# toolbox.net
KiCad netlist of a schematic drawn in EAGLE
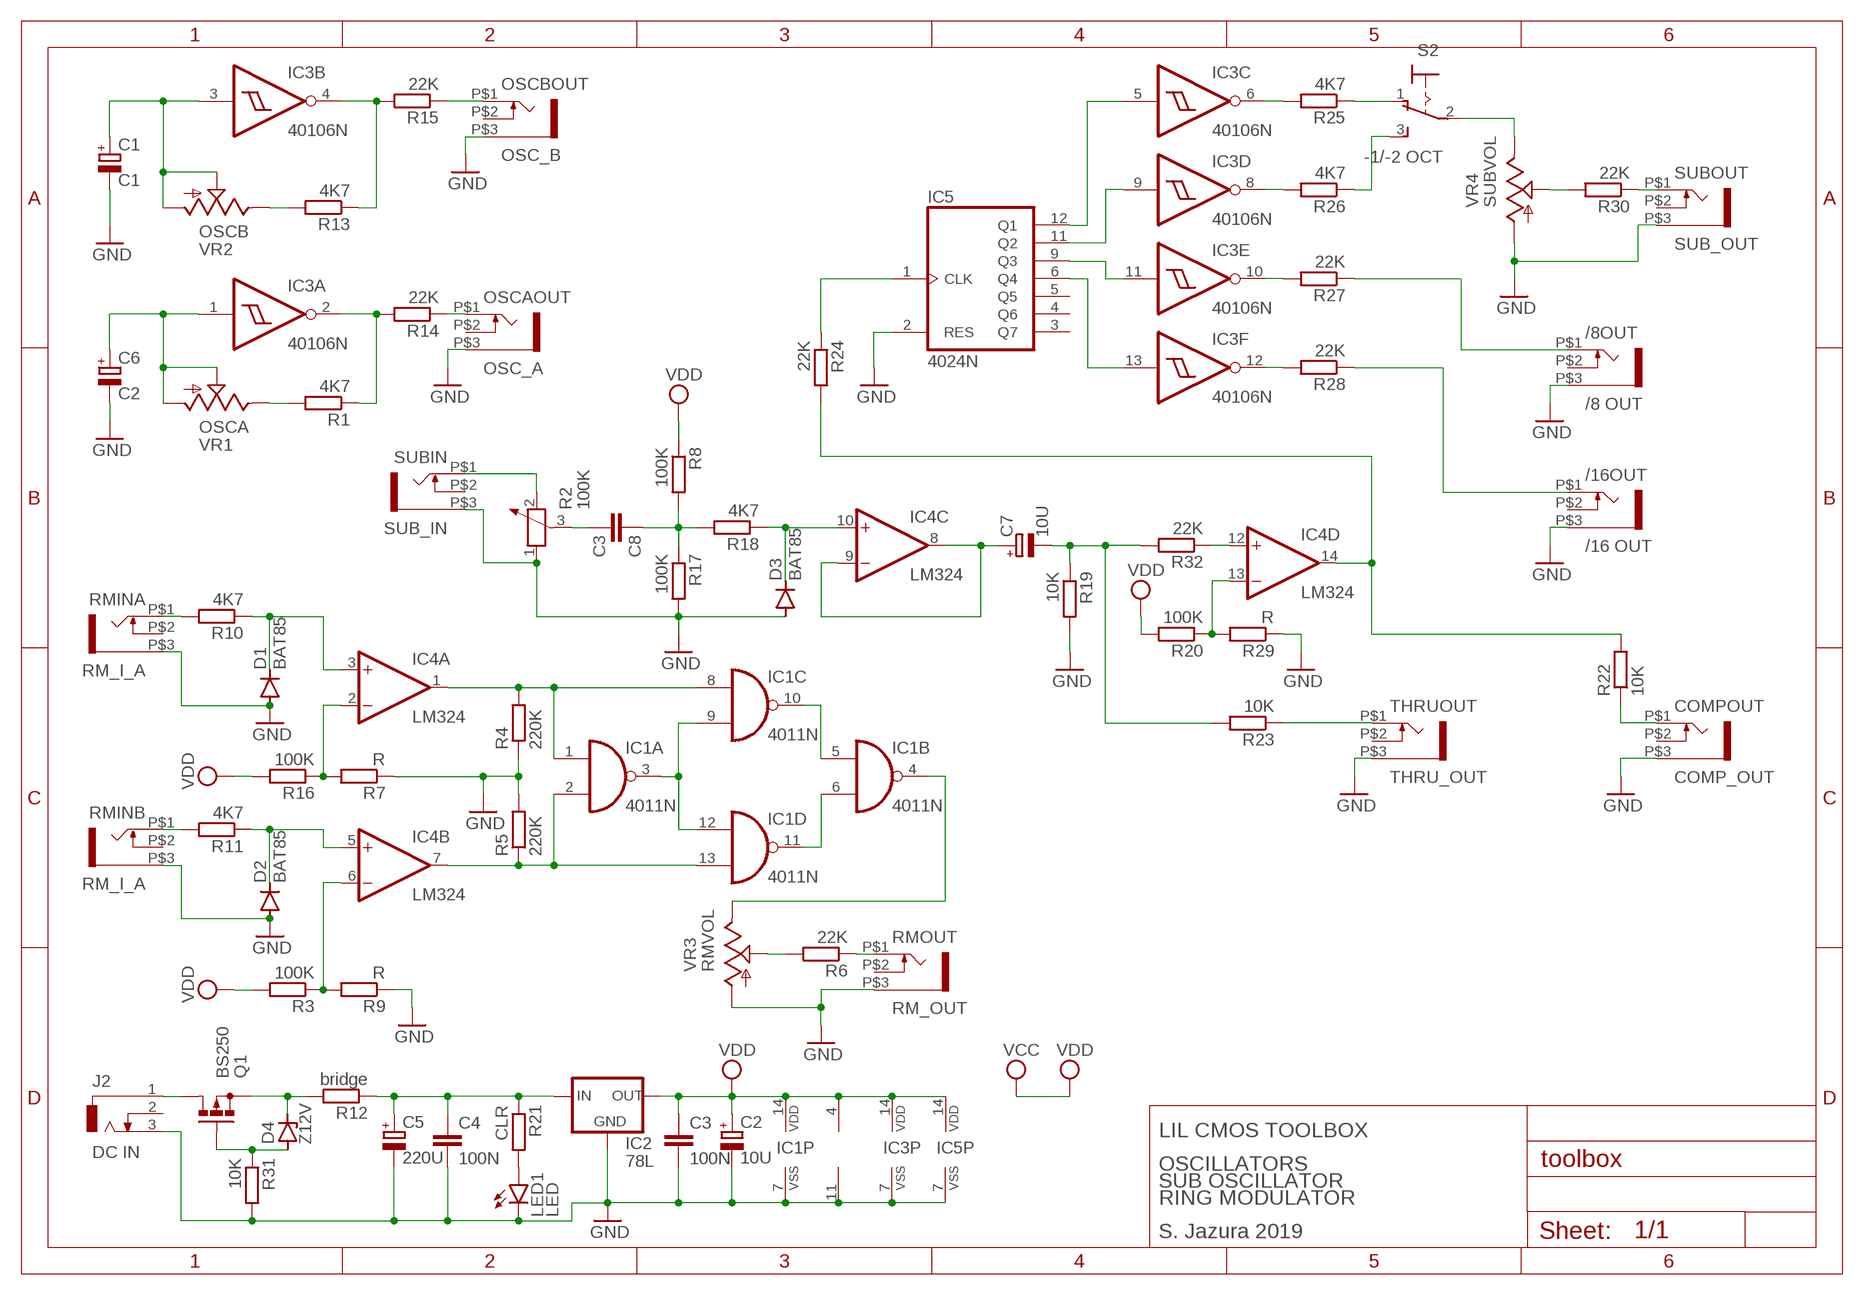
[diagram p0: schematic, sheet 1]

(export (version "E")
  (design (tool "Eeschema 10.0.6"))
  (components
    (comp (ref "/8OUT")
      (value "/8 OUT")
      (footprint "eagle-import:WQP-PJ301M-12_JACK")
      (libsource (lib "eagle-import") (part "WQP-PJ301M-12_JACK"))
    )
    (comp (ref "/16OUT")
      (value "/16 OUT")
      (footprint "eagle-import:WQP-PJ301M-12_JACK")
      (libsource (lib "eagle-import") (part "WQP-PJ301M-12_JACK"))
    )
    (comp (ref "C1")
      (value "C1")
      (footprint "eagle-import:000_4MM_CAP_STANDARD")
      (libsource (lib "eagle-import") (part "0_CPOL-EUE2-4"))
    )
    (comp (ref "C2")
      (value "10U")
      (footprint "eagle-import:000_4MM_CAP_STANDARD")
      (libsource (lib "eagle-import") (part "0_CPOL-EUE2-4"))
    )
    (comp (ref "C3")
      (value "100N")
      (footprint "eagle-import:000_5MM_DISC_STANDARD")
      (libsource (lib "eagle-import") (part "C-EU000_5MM_DISC"))
    )
    (comp (ref "C4")
      (value "100N")
      (footprint "eagle-import:000_5MM_DISC_STANDARD")
      (libsource (lib "eagle-import") (part "C-EU000_5MM_DISC"))
    )
    (comp (ref "C5")
      (value "220U")
      (footprint "eagle-import:E2,5-7")
      (libsource (lib "eagle-import") (part "CPOL-EUE2.5-7"))
    )
    (comp (ref "C6")
      (value "C2")
      (footprint "eagle-import:000_4MM_CAP_STANDARD")
      (libsource (lib "eagle-import") (part "0_CPOL-EUE2-4"))
    )
    (comp (ref "C7")
      (value "10U")
      (footprint "eagle-import:000_4MM_CAP_STANDARD")
      (libsource (lib "eagle-import") (part "0_CPOL-EUE2-4"))
    )
    (comp (ref "C8")
      (value "C3")
      (footprint "eagle-import:000_7,5MM_FOIL_STANDARD")
      (libsource (lib "eagle-import") (part "0_C-EU000_7,5MM_FOIL_STANDARD"))
    )
    (comp (ref "COMPOUT")
      (value "COMP_OUT")
      (footprint "eagle-import:WQP-PJ301M-12_JACK")
      (libsource (lib "eagle-import") (part "WQP-PJ301M-12_JACK"))
    )
    (comp (ref "D1")
      (value "BAT85")
      (footprint "eagle-import:DO35-7")
      (libsource (lib "eagle-import") (part "1N4148DO35-7"))
    )
    (comp (ref "D2")
      (value "BAT85")
      (footprint "eagle-import:DO35-7")
      (libsource (lib "eagle-import") (part "1N4148DO35-7"))
    )
    (comp (ref "D3")
      (value "BAT85")
      (footprint "eagle-import:DO35-7")
      (libsource (lib "eagle-import") (part "1N4148DO35-7"))
    )
    (comp (ref "D4")
      (value "Z12V")
      (footprint "eagle-import:DO34Z7")
      (libsource (lib "eagle-import") (part "BZV10"))
    )
    (comp (ref "IC1")
      (value "4011N")
      (footprint "eagle-import:DIL14")
      (libsource (lib "eagle-import") (part "4011N"))
    )
    (comp (ref "IC2")
      (value "78L")
      (footprint "eagle-import:000_78LXX_STANDARD")
      (libsource (lib "eagle-import") (part "78LXX"))
    )
    (comp (ref "IC3")
      (value "40106N")
      (footprint "eagle-import:DIL14")
      (libsource (lib "eagle-import") (part "40106N"))
    )
    (comp (ref "IC4")
      (value "LM324")
      (footprint "eagle-import:DIL14")
      (libsource (lib "eagle-import") (part "TL074P"))
    )
    (comp (ref "IC5")
      (value "4024N")
      (footprint "eagle-import:DIL14")
      (libsource (lib "eagle-import") (part "4024N"))
    )
    (comp (ref "J2")
      (value "DC IN")
      (footprint "eagle-import:DCJ0202")
      (libsource (lib "eagle-import") (part "DCJ0202"))
    )
    (comp (ref "LED1")
      (value "LED")
      (footprint "eagle-import:LED5MM")
      (libsource (lib "eagle-import") (part "LED5MM"))
    )
    (comp (ref "OSCAOUT")
      (value "OSC_A")
      (footprint "eagle-import:WQP-PJ301M-12_JACK")
      (libsource (lib "eagle-import") (part "WQP-PJ301M-12_JACK"))
    )
    (comp (ref "OSCBOUT")
      (value "OSC_B")
      (footprint "eagle-import:WQP-PJ301M-12_JACK")
      (libsource (lib "eagle-import") (part "WQP-PJ301M-12_JACK"))
    )
    (comp (ref "Q1")
      (value "BS250")
      (footprint "eagle-import:SOT54E")
      (libsource (lib "eagle-import") (part "BS250"))
    )
    (comp (ref "R1")
      (value "4K7")
      (footprint "eagle-import:000_7,5MM_STANDARD")
      (libsource (lib "eagle-import") (part "R-EU_000_7,5MM_STANDARD"))
    )
    (comp (ref "R2")
      (value "100K")
      (footprint "eagle-import:PT-10")
      (libsource (lib "eagle-import") (part "POTENTIOMETER_PT-10"))
    )
    (comp (ref "R3")
      (value "100K")
      (footprint "eagle-import:000_7,5MM_STANDARD")
      (libsource (lib "eagle-import") (part "R-EU_000_7,5MM_STANDARD"))
    )
    (comp (ref "R4")
      (value "220K")
      (footprint "eagle-import:000_7,5MM_STANDARD")
      (libsource (lib "eagle-import") (part "R-EU_000_7,5MM_STANDARD"))
    )
    (comp (ref "R5")
      (value "220K")
      (footprint "eagle-import:000_7,5MM_STANDARD")
      (libsource (lib "eagle-import") (part "R-EU_000_7,5MM_STANDARD"))
    )
    (comp (ref "R6")
      (value "22K")
      (footprint "eagle-import:000_7,5MM_STANDARD")
      (libsource (lib "eagle-import") (part "R-EU_000_7,5MM_STANDARD"))
    )
    (comp (ref "R7")
      (value "R")
      (footprint "eagle-import:000_7,5MM_STANDARD")
      (libsource (lib "eagle-import") (part "R-EU_000_7,5MM_STANDARD"))
    )
    (comp (ref "R8")
      (value "100K")
      (footprint "eagle-import:000_7,5MM_STANDARD")
      (libsource (lib "eagle-import") (part "R-EU_000_7,5MM_STANDARD"))
    )
    (comp (ref "R9")
      (value "R")
      (footprint "eagle-import:000_7,5MM_STANDARD")
      (libsource (lib "eagle-import") (part "R-EU_000_7,5MM_STANDARD"))
    )
    (comp (ref "R10")
      (value "4K7")
      (footprint "eagle-import:000_7,5MM_STANDARD")
      (libsource (lib "eagle-import") (part "R-EU_000_7,5MM_STANDARD"))
    )
    (comp (ref "R11")
      (value "4K7")
      (footprint "eagle-import:000_7,5MM_STANDARD")
      (libsource (lib "eagle-import") (part "R-EU_000_7,5MM_STANDARD"))
    )
    (comp (ref "R12")
      (value "bridge")
      (footprint "eagle-import:000_7,5MM_STANDARD")
      (libsource (lib "eagle-import") (part "R-EU_000_7,5MM_STANDARD"))
    )
    (comp (ref "R13")
      (value "4K7")
      (footprint "eagle-import:000_7,5MM_STANDARD")
      (libsource (lib "eagle-import") (part "R-EU_000_7,5MM_STANDARD"))
    )
    (comp (ref "R14")
      (value "22K")
      (footprint "eagle-import:000_7,5MM_STANDARD")
      (libsource (lib "eagle-import") (part "R-EU_000_7,5MM_STANDARD"))
    )
    (comp (ref "R15")
      (value "22K")
      (footprint "eagle-import:000_7,5MM_STANDARD")
      (libsource (lib "eagle-import") (part "R-EU_000_7,5MM_STANDARD"))
    )
    (comp (ref "R16")
      (value "100K")
      (footprint "eagle-import:000_7,5MM_STANDARD")
      (libsource (lib "eagle-import") (part "R-EU_000_7,5MM_STANDARD"))
    )
    (comp (ref "R17")
      (value "100K")
      (footprint "eagle-import:000_7,5MM_STANDARD")
      (libsource (lib "eagle-import") (part "R-EU_000_7,5MM_STANDARD"))
    )
    (comp (ref "R18")
      (value "4K7")
      (footprint "eagle-import:000_7,5MM_STANDARD")
      (libsource (lib "eagle-import") (part "R-EU_000_7,5MM_STANDARD"))
    )
    (comp (ref "R19")
      (value "10K")
      (footprint "eagle-import:000_7,5MM_STANDARD")
      (libsource (lib "eagle-import") (part "R-EU_000_7,5MM_STANDARD"))
    )
    (comp (ref "R20")
      (value "100K")
      (footprint "eagle-import:000_7,5MM_STANDARD")
      (libsource (lib "eagle-import") (part "R-EU_000_7,5MM_STANDARD"))
    )
    (comp (ref "R21")
      (value "CLR")
      (footprint "eagle-import:000_7,5MM_STANDARD")
      (libsource (lib "eagle-import") (part "R-EU_000_7,5MM_STANDARD"))
    )
    (comp (ref "R22")
      (value "10K")
      (footprint "eagle-import:000_7,5MM_STANDARD")
      (libsource (lib "eagle-import") (part "R-EU_000_7,5MM_STANDARD"))
    )
    (comp (ref "R23")
      (value "10K")
      (footprint "eagle-import:000_7,5MM_STANDARD")
      (libsource (lib "eagle-import") (part "R-EU_000_7,5MM_STANDARD"))
    )
    (comp (ref "R24")
      (value "22K")
      (footprint "eagle-import:000_7,5MM_STANDARD")
      (libsource (lib "eagle-import") (part "R-EU_000_7,5MM_STANDARD"))
    )
    (comp (ref "R25")
      (value "4K7")
      (footprint "eagle-import:000_7,5MM_STANDARD")
      (libsource (lib "eagle-import") (part "R-EU_000_7,5MM_STANDARD"))
    )
    (comp (ref "R26")
      (value "4K7")
      (footprint "eagle-import:000_7,5MM_STANDARD")
      (libsource (lib "eagle-import") (part "R-EU_000_7,5MM_STANDARD"))
    )
    (comp (ref "R27")
      (value "22K")
      (footprint "eagle-import:000_7,5MM_STANDARD")
      (libsource (lib "eagle-import") (part "R-EU_000_7,5MM_STANDARD"))
    )
    (comp (ref "R28")
      (value "22K")
      (footprint "eagle-import:000_7,5MM_STANDARD")
      (libsource (lib "eagle-import") (part "R-EU_000_7,5MM_STANDARD"))
    )
    (comp (ref "R29")
      (value "R")
      (footprint "eagle-import:000_7,5MM_STANDARD")
      (libsource (lib "eagle-import") (part "R-EU_000_7,5MM_STANDARD"))
    )
    (comp (ref "R30")
      (value "22K")
      (footprint "eagle-import:000_7,5MM_STANDARD")
      (libsource (lib "eagle-import") (part "R-EU_000_7,5MM_STANDARD"))
    )
    (comp (ref "R31")
      (value "10K")
      (footprint "eagle-import:000_7,5MM_STANDARD")
      (libsource (lib "eagle-import") (part "R-EU_000_7,5MM_STANDARD"))
    )
    (comp (ref "R32")
      (value "22K")
      (footprint "eagle-import:000_7,5MM_STANDARD")
      (libsource (lib "eagle-import") (part "R-EU_000_7,5MM_STANDARD"))
    )
    (comp (ref "RMINA")
      (value "RM_I_A")
      (footprint "eagle-import:WQP-PJ301M-12_JACK")
      (libsource (lib "eagle-import") (part "WQP-PJ301M-12_JACK"))
    )
    (comp (ref "RMINB")
      (value "RM_I_A")
      (footprint "eagle-import:WQP-PJ301M-12_JACK")
      (libsource (lib "eagle-import") (part "WQP-PJ301M-12_JACK"))
    )
    (comp (ref "RMOUT")
      (value "RM_OUT")
      (footprint "eagle-import:WQP-PJ301M-12_JACK")
      (libsource (lib "eagle-import") (part "WQP-PJ301M-12_JACK"))
    )
    (comp (ref "S2")
      (value "-1/-2 OCT")
      (footprint "eagle-import:M9040P")
      (libsource (lib "eagle-import") (part "SPDT_LUG_PCMOUNT"))
    )
    (comp (ref "SUBIN")
      (value "SUB_IN")
      (footprint "eagle-import:WQP-PJ301M-12_JACK")
      (libsource (lib "eagle-import") (part "WQP-PJ301M-12_JACK"))
    )
    (comp (ref "SUBOUT")
      (value "SUB_OUT")
      (footprint "eagle-import:WQP-PJ301M-12_JACK")
      (libsource (lib "eagle-import") (part "WQP-PJ301M-12_JACK"))
    )
    (comp (ref "THRUOUT")
      (value "THRU_OUT")
      (footprint "eagle-import:WQP-PJ301M-12_JACK")
      (libsource (lib "eagle-import") (part "WQP-PJ301M-12_JACK"))
    )
    (comp (ref "VR1")
      (value "OSCA")
      (footprint "eagle-import:9MM_SNAP-IN_POT")
      (libsource (lib "eagle-import") (part "9MM_SNAP-IN_POT_"))
    )
    (comp (ref "VR2")
      (value "OSCB")
      (footprint "eagle-import:9MM_SNAP-IN_POT")
      (libsource (lib "eagle-import") (part "9MM_SNAP-IN_POT_"))
    )
    (comp (ref "VR3")
      (value "RMVOL")
      (footprint "eagle-import:9MM_SNAP-IN_POT")
      (libsource (lib "eagle-import") (part "9MM_SNAP-IN_POT_"))
    )
    (comp (ref "VR4")
      (value "SUBVOL")
      (footprint "eagle-import:9MM_SNAP-IN_POT")
      (libsource (lib "eagle-import") (part "9MM_SNAP-IN_POT_"))
    )
  )
  (nets
    (net (code "1") (name "GND") (class "Default")
      (node (ref "/16OUT") (pin "P$3") (pinfunction "1_P$3") (pintype "passive"))
      (node (ref "/8OUT") (pin "P$3") (pinfunction "1_P$3") (pintype "passive"))
      (node (ref "C1") (pin "-") (pinfunction "-_-") (pintype "passive"))
      (node (ref "C2") (pin "-") (pinfunction "-_-") (pintype "passive"))
      (node (ref "C3") (pin "2") (pinfunction "2_2") (pintype "passive"))
      (node (ref "C4") (pin "2") (pinfunction "2_2") (pintype "passive"))
      (node (ref "C5") (pin "-") (pinfunction "-_-") (pintype "passive"))
      (node (ref "C6") (pin "-") (pinfunction "-_-") (pintype "passive"))
      (node (ref "COMPOUT") (pin "P$3") (pinfunction "1_P$3") (pintype "passive"))
      (node (ref "D1") (pin "A") (pinfunction "A_A") (pintype "passive"))
      (node (ref "D2") (pin "A") (pinfunction "A_A") (pintype "passive"))
      (node (ref "D3") (pin "A") (pinfunction "A_A") (pintype "passive"))
      (node (ref "IC1") (pin "7") (pinfunction "VSS_7") (pintype "power_in"))
      (node (ref "IC2") (pin "GND") (pinfunction "GND_GND") (pintype "input"))
      (node (ref "IC3") (pin "7") (pinfunction "VSS_7") (pintype "power_in"))
      (node (ref "IC4") (pin "11") (pinfunction "V-_11") (pintype "power_in"))
      (node (ref "IC5") (pin "2") (pinfunction "RES_2") (pintype "input"))
      (node (ref "IC5") (pin "7") (pinfunction "VSS_7") (pintype "power_in"))
      (node (ref "J2") (pin "3") (pinfunction "3_3") (pintype "passive"))
      (node (ref "LED1") (pin "K") (pinfunction "C_K") (pintype "passive"))
      (node (ref "OSCAOUT") (pin "P$3") (pinfunction "1_P$3") (pintype "passive"))
      (node (ref "OSCBOUT") (pin "P$3") (pinfunction "1_P$3") (pintype "passive"))
      (node (ref "R17") (pin "2") (pinfunction "2_2") (pintype "passive"))
      (node (ref "R19") (pin "2") (pinfunction "2_2") (pintype "passive"))
      (node (ref "R2") (pin "1") (pinfunction "1_1") (pintype "passive"))
      (node (ref "R29") (pin "1") (pinfunction "1_1") (pintype "passive"))
      (node (ref "R31") (pin "2") (pinfunction "2_2") (pintype "passive"))
      (node (ref "R4") (pin "1") (pinfunction "1_1") (pintype "passive"))
      (node (ref "R5") (pin "2") (pinfunction "2_2") (pintype "passive"))
      (node (ref "R7") (pin "1") (pinfunction "1_1") (pintype "passive"))
      (node (ref "R9") (pin "1") (pinfunction "1_1") (pintype "passive"))
      (node (ref "RMINA") (pin "P$3") (pinfunction "1_P$3") (pintype "passive"))
      (node (ref "RMINB") (pin "P$3") (pinfunction "1_P$3") (pintype "passive"))
      (node (ref "RMOUT") (pin "P$3") (pinfunction "1_P$3") (pintype "passive"))
      (node (ref "SUBIN") (pin "P$3") (pinfunction "1_P$3") (pintype "passive"))
      (node (ref "SUBOUT") (pin "P$3") (pinfunction "1_P$3") (pintype "passive"))
      (node (ref "THRUOUT") (pin "P$3") (pinfunction "1_P$3") (pintype "passive"))
      (node (ref "VR3") (pin "1") (pinfunction "A_1") (pintype "passive"))
      (node (ref "VR4") (pin "1") (pinfunction "A_1") (pintype "passive"))
    )
    (net (code "2") (name "Net-(/8OUT-2)") (class "Default")
      (node (ref "/8OUT") (pin "P$1") (pinfunction "2_P$1") (pintype "passive"))
      (node (ref "R27") (pin "1") (pinfunction "1_1") (pintype "passive"))
    )
    (net (code "3") (name "Net-(/16OUT-2)") (class "Default")
      (node (ref "/16OUT") (pin "P$1") (pinfunction "2_P$1") (pintype "passive"))
      (node (ref "R28") (pin "1") (pinfunction "1_1") (pintype "passive"))
    )
    (net (code "4") (name "Net-(C4-Pad1)") (class "Default")
      (node (ref "C4") (pin "1") (pinfunction "1_1") (pintype "passive"))
      (node (ref "C5") (pin "+") (pinfunction "+_+") (pintype "passive"))
      (node (ref "IC2") (pin "IN") (pinfunction "IN_IN") (pintype "input"))
      (node (ref "R12") (pin "1") (pinfunction "1_1") (pintype "passive"))
      (node (ref "R21") (pin "1") (pinfunction "1_1") (pintype "passive"))
    )
    (net (code "5") (name "Net-(C7-Pad-)") (class "Default")
      (node (ref "C7") (pin "-") (pinfunction "-_-") (pintype "passive"))
      (node (ref "R19") (pin "1") (pinfunction "1_1") (pintype "passive"))
      (node (ref "R23") (pin "2") (pinfunction "2_2") (pintype "passive"))
      (node (ref "R32") (pin "2") (pinfunction "2_2") (pintype "passive"))
    )
    (net (code "6") (name "Net-(C8-Pad1)") (class "Default")
      (node (ref "C8") (pin "1") (pinfunction "1_1") (pintype "passive"))
      (node (ref "R17") (pin "1") (pinfunction "1_1") (pintype "passive"))
      (node (ref "R18") (pin "2") (pinfunction "2_2") (pintype "passive"))
      (node (ref "R8") (pin "2") (pinfunction "2_2") (pintype "passive"))
    )
    (net (code "7") (name "Net-(C8-Pad2)") (class "Default")
      (node (ref "C8") (pin "2") (pinfunction "2_2") (pintype "passive"))
      (node (ref "R2") (pin "3") (pinfunction "3_3") (pintype "passive"))
    )
    (net (code "8") (name "Net-(COMPOUT-2)") (class "Default")
      (node (ref "COMPOUT") (pin "P$1") (pinfunction "2_P$1") (pintype "passive"))
      (node (ref "R22") (pin "1") (pinfunction "1_1") (pintype "passive"))
    )
    (net (code "9") (name "Net-(D4-PadA)") (class "Default")
      (node (ref "D4") (pin "A") (pinfunction "A_A") (pintype "passive"))
      (node (ref "Q1") (pin "G") (pinfunction "G_G") (pintype "passive"))
      (node (ref "R31") (pin "1") (pinfunction "1_1") (pintype "passive"))
    )
    (net (code "10") (name "Net-(D4-PadC)") (class "Default")
      (node (ref "D4") (pin "C") (pinfunction "C_C") (pintype "passive"))
      (node (ref "Q1") (pin "S") (pinfunction "S_S") (pintype "passive"))
      (node (ref "R12") (pin "2") (pinfunction "2_2") (pintype "passive"))
    )
    (net (code "11") (name "Net-(IC1A-I0)") (class "Default")
      (node (ref "IC1") (pin "1") (pinfunction "I0_1") (pintype "input"))
      (node (ref "IC1") (pin "8") (pinfunction "I0_8") (pintype "input"))
      (node (ref "IC4") (pin "1") (pinfunction "OUT_1") (pintype "output"))
      (node (ref "R4") (pin "2") (pinfunction "2_2") (pintype "passive"))
    )
    (net (code "12") (name "Net-(IC1A-I1)") (class "Default")
      (node (ref "IC1") (pin "13") (pinfunction "I1_13") (pintype "input"))
      (node (ref "IC1") (pin "2") (pinfunction "I1_2") (pintype "input"))
      (node (ref "IC4") (pin "7") (pinfunction "OUT_7") (pintype "output"))
      (node (ref "R5") (pin "1") (pinfunction "1_1") (pintype "passive"))
    )
    (net (code "13") (name "Net-(IC1A-O)") (class "Default")
      (node (ref "IC1") (pin "12") (pinfunction "I0_12") (pintype "input"))
      (node (ref "IC1") (pin "3") (pinfunction "O_3") (pintype "output"))
      (node (ref "IC1") (pin "9") (pinfunction "I1_9") (pintype "input"))
    )
    (net (code "14") (name "Net-(IC1B-I0)") (class "Default")
      (node (ref "IC1") (pin "10") (pinfunction "O_10") (pintype "output"))
      (node (ref "IC1") (pin "5") (pinfunction "I0_5") (pintype "input"))
    )
    (net (code "15") (name "Net-(IC1B-I1)") (class "Default")
      (node (ref "IC1") (pin "11") (pinfunction "O_11") (pintype "output"))
      (node (ref "IC1") (pin "6") (pinfunction "I1_6") (pintype "input"))
    )
    (net (code "16") (name "Net-(IC1B-O)") (class "Default")
      (node (ref "IC1") (pin "4") (pinfunction "O_4") (pintype "output"))
      (node (ref "VR3") (pin "3") (pinfunction "E_3") (pintype "passive"))
    )
    (net (code "17") (name "Net-(IC3A-I)") (class "Default")
      (node (ref "C6") (pin "+") (pinfunction "+_+") (pintype "passive"))
      (node (ref "IC3") (pin "1") (pinfunction "I_1") (pintype "input"))
      (node (ref "VR1") (pin "1") (pinfunction "A_1") (pintype "passive"))
      (node (ref "VR1") (pin "2") (pinfunction "S_2") (pintype "passive"))
    )
    (net (code "18") (name "Net-(IC3A-O)") (class "Default")
      (node (ref "IC3") (pin "2") (pinfunction "O_2") (pintype "output"))
      (node (ref "R1") (pin "1") (pinfunction "1_1") (pintype "passive"))
      (node (ref "R14") (pin "2") (pinfunction "2_2") (pintype "passive"))
    )
    (net (code "19") (name "Net-(IC3B-I)") (class "Default")
      (node (ref "C1") (pin "+") (pinfunction "+_+") (pintype "passive"))
      (node (ref "IC3") (pin "3") (pinfunction "I_3") (pintype "input"))
      (node (ref "VR2") (pin "1") (pinfunction "A_1") (pintype "passive"))
      (node (ref "VR2") (pin "2") (pinfunction "S_2") (pintype "passive"))
    )
    (net (code "20") (name "Net-(IC3B-O)") (class "Default")
      (node (ref "IC3") (pin "4") (pinfunction "O_4") (pintype "output"))
      (node (ref "R13") (pin "1") (pinfunction "1_1") (pintype "passive"))
      (node (ref "R15") (pin "2") (pinfunction "2_2") (pintype "passive"))
    )
    (net (code "21") (name "Net-(IC3C-I)") (class "Default")
      (node (ref "IC3") (pin "5") (pinfunction "I_5") (pintype "input"))
      (node (ref "IC5") (pin "12") (pinfunction "Q1_12") (pintype "output"))
    )
    (net (code "22") (name "Net-(IC3C-O)") (class "Default")
      (node (ref "IC3") (pin "6") (pinfunction "O_6") (pintype "output"))
      (node (ref "R25") (pin "2") (pinfunction "2_2") (pintype "passive"))
    )
    (net (code "23") (name "Net-(IC3D-I)") (class "Default")
      (node (ref "IC3") (pin "9") (pinfunction "I_9") (pintype "input"))
      (node (ref "IC5") (pin "11") (pinfunction "Q2_11") (pintype "output"))
    )
    (net (code "24") (name "Net-(IC3D-O)") (class "Default")
      (node (ref "IC3") (pin "8") (pinfunction "O_8") (pintype "output"))
      (node (ref "R26") (pin "2") (pinfunction "2_2") (pintype "passive"))
    )
    (net (code "25") (name "Net-(IC3E-I)") (class "Default")
      (node (ref "IC3") (pin "11") (pinfunction "I_11") (pintype "input"))
      (node (ref "IC5") (pin "9") (pinfunction "Q3_9") (pintype "output"))
    )
    (net (code "26") (name "Net-(IC3E-O)") (class "Default")
      (node (ref "IC3") (pin "10") (pinfunction "O_10") (pintype "output"))
      (node (ref "R27") (pin "2") (pinfunction "2_2") (pintype "passive"))
    )
    (net (code "27") (name "Net-(IC3F-I)") (class "Default")
      (node (ref "IC3") (pin "13") (pinfunction "I_13") (pintype "input"))
      (node (ref "IC5") (pin "6") (pinfunction "Q4_6") (pintype "output"))
    )
    (net (code "28") (name "Net-(IC3F-O)") (class "Default")
      (node (ref "IC3") (pin "12") (pinfunction "O_12") (pintype "output"))
      (node (ref "R28") (pin "2") (pinfunction "2_2") (pintype "passive"))
    )
    (net (code "29") (name "Net-(IC4A-+IN)") (class "Default")
      (node (ref "D1") (pin "C") (pinfunction "C_C") (pintype "passive"))
      (node (ref "IC4") (pin "3") (pinfunction "+IN_3") (pintype "input"))
      (node (ref "R10") (pin "1") (pinfunction "1_1") (pintype "passive"))
    )
    (net (code "30") (name "Net-(IC4A--IN)") (class "Default")
      (node (ref "IC4") (pin "2") (pinfunction "-IN_2") (pintype "input"))
      (node (ref "R16") (pin "1") (pinfunction "1_1") (pintype "passive"))
      (node (ref "R7") (pin "2") (pinfunction "2_2") (pintype "passive"))
    )
    (net (code "31") (name "Net-(IC4B-+IN)") (class "Default")
      (node (ref "D2") (pin "C") (pinfunction "C_C") (pintype "passive"))
      (node (ref "IC4") (pin "5") (pinfunction "+IN_5") (pintype "input"))
      (node (ref "R11") (pin "1") (pinfunction "1_1") (pintype "passive"))
    )
    (net (code "32") (name "Net-(IC4B--IN)") (class "Default")
      (node (ref "IC4") (pin "6") (pinfunction "-IN_6") (pintype "input"))
      (node (ref "R3") (pin "1") (pinfunction "1_1") (pintype "passive"))
      (node (ref "R9") (pin "2") (pinfunction "2_2") (pintype "passive"))
    )
    (net (code "33") (name "Net-(IC4C-+IN)") (class "Default")
      (node (ref "D3") (pin "C") (pinfunction "C_C") (pintype "passive"))
      (node (ref "IC4") (pin "10") (pinfunction "+IN_10") (pintype "input"))
      (node (ref "R18") (pin "1") (pinfunction "1_1") (pintype "passive"))
    )
    (net (code "34") (name "Net-(IC4C--IN)") (class "Default")
      (node (ref "C7") (pin "+") (pinfunction "+_+") (pintype "passive"))
      (node (ref "IC4") (pin "8") (pinfunction "OUT_8") (pintype "output"))
      (node (ref "IC4") (pin "9") (pinfunction "-IN_9") (pintype "input"))
    )
    (net (code "35") (name "Net-(IC4D-+IN)") (class "Default")
      (node (ref "IC4") (pin "12") (pinfunction "+IN_12") (pintype "input"))
      (node (ref "R32") (pin "1") (pinfunction "1_1") (pintype "passive"))
    )
    (net (code "36") (name "Net-(IC4D--IN)") (class "Default")
      (node (ref "IC4") (pin "13") (pinfunction "-IN_13") (pintype "input"))
      (node (ref "R20") (pin "1") (pinfunction "1_1") (pintype "passive"))
      (node (ref "R29") (pin "2") (pinfunction "2_2") (pintype "passive"))
    )
    (net (code "37") (name "Net-(IC4D-OUT)") (class "Default")
      (node (ref "IC4") (pin "14") (pinfunction "OUT_14") (pintype "output"))
      (node (ref "R22") (pin "2") (pinfunction "2_2") (pintype "passive"))
      (node (ref "R24") (pin "2") (pinfunction "2_2") (pintype "passive"))
    )
    (net (code "38") (name "Net-(IC5A-CLK)") (class "Default")
      (node (ref "IC5") (pin "1") (pinfunction "CLK_1") (pintype "input"))
      (node (ref "R24") (pin "1") (pinfunction "1_1") (pintype "passive"))
    )
    (net (code "39") (name "Net-(J2-Pad1)") (class "Default")
      (node (ref "J2") (pin "1") (pinfunction "1_1") (pintype "passive"))
      (node (ref "Q1") (pin "D") (pinfunction "D_D") (pintype "passive"))
    )
    (net (code "40") (name "Net-(LED1-PadA)") (class "Default")
      (node (ref "LED1") (pin "A") (pinfunction "A_A") (pintype "passive"))
      (node (ref "R21") (pin "2") (pinfunction "2_2") (pintype "passive"))
    )
    (net (code "41") (name "Net-(OSCAOUT-2)") (class "Default")
      (node (ref "OSCAOUT") (pin "P$1") (pinfunction "2_P$1") (pintype "passive"))
      (node (ref "R14") (pin "1") (pinfunction "1_1") (pintype "passive"))
    )
    (net (code "42") (name "Net-(OSCBOUT-2)") (class "Default")
      (node (ref "OSCBOUT") (pin "P$1") (pinfunction "2_P$1") (pintype "passive"))
      (node (ref "R15") (pin "1") (pinfunction "1_1") (pintype "passive"))
    )
    (net (code "43") (name "Net-(RMINA-2)") (class "Default")
      (node (ref "R10") (pin "2") (pinfunction "2_2") (pintype "passive"))
      (node (ref "RMINA") (pin "P$1") (pinfunction "2_P$1") (pintype "passive"))
    )
    (net (code "44") (name "Net-(RMINB-2)") (class "Default")
      (node (ref "R11") (pin "2") (pinfunction "2_2") (pintype "passive"))
      (node (ref "RMINB") (pin "P$1") (pinfunction "2_P$1") (pintype "passive"))
    )
    (net (code "45") (name "Net-(RMOUT-2)") (class "Default")
      (node (ref "R6") (pin "1") (pinfunction "1_1") (pintype "passive"))
      (node (ref "RMOUT") (pin "P$1") (pinfunction "2_P$1") (pintype "passive"))
    )
    (net (code "46") (name "Net-(S2-O)") (class "Default")
      (node (ref "R25") (pin "1") (pinfunction "1_1") (pintype "passive"))
      (node (ref "S2") (pin "1") (pinfunction "O_1") (pintype "passive"))
    )
    (net (code "47") (name "Net-(S2-P)") (class "Default")
      (node (ref "S2") (pin "2") (pinfunction "P_2") (pintype "passive"))
      (node (ref "VR4") (pin "3") (pinfunction "E_3") (pintype "passive"))
    )
    (net (code "48") (name "Net-(S2-S)") (class "Default")
      (node (ref "R26") (pin "1") (pinfunction "1_1") (pintype "passive"))
      (node (ref "S2") (pin "3") (pinfunction "S_3") (pintype "passive"))
    )
    (net (code "49") (name "Net-(SUBIN-2)") (class "Default")
      (node (ref "R2") (pin "2") (pinfunction "2_2") (pintype "passive"))
      (node (ref "SUBIN") (pin "P$1") (pinfunction "2_P$1") (pintype "passive"))
    )
    (net (code "50") (name "Net-(SUBOUT-2)") (class "Default")
      (node (ref "R30") (pin "1") (pinfunction "1_1") (pintype "passive"))
      (node (ref "SUBOUT") (pin "P$1") (pinfunction "2_P$1") (pintype "passive"))
    )
    (net (code "51") (name "Net-(THRUOUT-2)") (class "Default")
      (node (ref "R23") (pin "1") (pinfunction "1_1") (pintype "passive"))
      (node (ref "THRUOUT") (pin "P$1") (pinfunction "2_P$1") (pintype "passive"))
    )
    (net (code "52") (name "Net-(VR1-E)") (class "Default")
      (node (ref "R1") (pin "2") (pinfunction "2_2") (pintype "passive"))
      (node (ref "VR1") (pin "3") (pinfunction "E_3") (pintype "passive"))
    )
    (net (code "53") (name "Net-(VR2-E)") (class "Default")
      (node (ref "R13") (pin "2") (pinfunction "2_2") (pintype "passive"))
      (node (ref "VR2") (pin "3") (pinfunction "E_3") (pintype "passive"))
    )
    (net (code "54") (name "Net-(VR3-S)") (class "Default")
      (node (ref "R6") (pin "2") (pinfunction "2_2") (pintype "passive"))
      (node (ref "VR3") (pin "2") (pinfunction "S_2") (pintype "passive"))
    )
    (net (code "55") (name "Net-(VR4-S)") (class "Default")
      (node (ref "R30") (pin "2") (pinfunction "2_2") (pintype "passive"))
      (node (ref "VR4") (pin "2") (pinfunction "S_2") (pintype "passive"))
    )
    (net (code "56") (name "VCC") (class "Default")
      (node (ref "C2") (pin "+") (pinfunction "+_+") (pintype "passive"))
      (node (ref "C3") (pin "1") (pinfunction "1_1") (pintype "passive"))
      (node (ref "IC1") (pin "14") (pinfunction "VDD_14") (pintype "power_in"))
      (node (ref "IC2") (pin "OUT") (pinfunction "OUT_OUT") (pintype "passive"))
      (node (ref "IC3") (pin "14") (pinfunction "VDD_14") (pintype "power_in"))
      (node (ref "IC4") (pin "4") (pinfunction "V+_4") (pintype "power_in"))
      (node (ref "IC5") (pin "14") (pinfunction "VDD_14") (pintype "power_in"))
      (node (ref "R16") (pin "2") (pinfunction "2_2") (pintype "passive"))
      (node (ref "R20") (pin "2") (pinfunction "2_2") (pintype "passive"))
      (node (ref "R3") (pin "2") (pinfunction "2_2") (pintype "passive"))
      (node (ref "R8") (pin "1") (pinfunction "1_1") (pintype "passive"))
    )
    (net (code "57") (name "unconnected-(/8OUT-3-PadP$2)") (class "Default")
      (node (ref "/8OUT") (pin "P$2") (pinfunction "3_P$2") (pintype "passive"))
    )
    (net (code "58") (name "unconnected-(/16OUT-3-PadP$2)") (class "Default")
      (node (ref "/16OUT") (pin "P$2") (pinfunction "3_P$2") (pintype "passive"))
    )
    (net (code "59") (name "unconnected-(COMPOUT-3-PadP$2)") (class "Default")
      (node (ref "COMPOUT") (pin "P$2") (pinfunction "3_P$2") (pintype "passive"))
    )
    (net (code "60") (name "unconnected-(IC5A-Q5-Pad5)") (class "Default")
      (node (ref "IC5") (pin "5") (pinfunction "Q5_5") (pintype "output"))
    )
    (net (code "61") (name "unconnected-(IC5A-Q6-Pad4)") (class "Default")
      (node (ref "IC5") (pin "4") (pinfunction "Q6_4") (pintype "output"))
    )
    (net (code "62") (name "unconnected-(IC5A-Q7-Pad3)") (class "Default")
      (node (ref "IC5") (pin "3") (pinfunction "Q7_3") (pintype "output"))
    )
    (net (code "63") (name "unconnected-(J2-Pad2)") (class "Default")
      (node (ref "J2") (pin "2") (pinfunction "2_2") (pintype "passive"))
    )
    (net (code "64") (name "unconnected-(OSCAOUT-3-PadP$2)") (class "Default")
      (node (ref "OSCAOUT") (pin "P$2") (pinfunction "3_P$2") (pintype "passive"))
    )
    (net (code "65") (name "unconnected-(OSCBOUT-3-PadP$2)") (class "Default")
      (node (ref "OSCBOUT") (pin "P$2") (pinfunction "3_P$2") (pintype "passive"))
    )
    (net (code "66") (name "unconnected-(RMINA-3-PadP$2)") (class "Default")
      (node (ref "RMINA") (pin "P$2") (pinfunction "3_P$2") (pintype "passive"))
    )
    (net (code "67") (name "unconnected-(RMINB-3-PadP$2)") (class "Default")
      (node (ref "RMINB") (pin "P$2") (pinfunction "3_P$2") (pintype "passive"))
    )
    (net (code "68") (name "unconnected-(RMOUT-3-PadP$2)") (class "Default")
      (node (ref "RMOUT") (pin "P$2") (pinfunction "3_P$2") (pintype "passive"))
    )
    (net (code "69") (name "unconnected-(SUBIN-3-PadP$2)") (class "Default")
      (node (ref "SUBIN") (pin "P$2") (pinfunction "3_P$2") (pintype "passive"))
    )
    (net (code "70") (name "unconnected-(SUBOUT-3-PadP$2)") (class "Default")
      (node (ref "SUBOUT") (pin "P$2") (pinfunction "3_P$2") (pintype "passive"))
    )
    (net (code "71") (name "unconnected-(THRUOUT-3-PadP$2)") (class "Default")
      (node (ref "THRUOUT") (pin "P$2") (pinfunction "3_P$2") (pintype "passive"))
    )
  )
)
